# CAN.net
KiCad netlist of a schematic drawn in Altium Designer
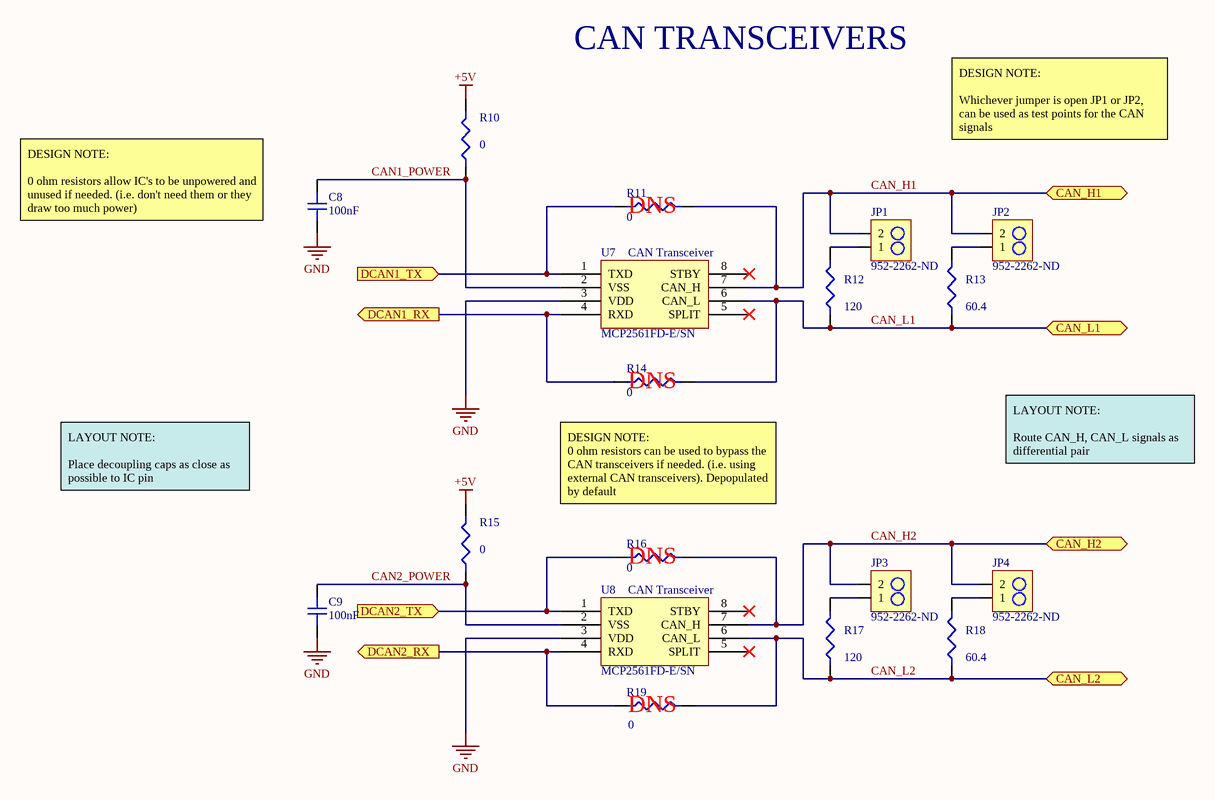
[diagram p0: CAN.SchDoc]

(export (version "E")
  (design (tool "Eeschema 10.0.6"))
  (components
    (comp (ref "C8")
      (value "100nF")
      (footprint "PHANTOM_FOOTPRINTS:C0805")
      (description "CAP MLCC 100nF 10Volts U2J 5%")
      (fields
        (field (name "MANUFACTURER") "Murata")
        (field (name "MANUFACTURER PART NUMBER") "GRM21B7U1A104JA01L")
      )
      (libsource (lib "PHANTOM_LIBRARY") (part "GRM21B7U1A104JA01L"))
    )
    (comp (ref "C9")
      (value "100nF")
      (footprint "PHANTOM_FOOTPRINTS:C0805")
      (description "CAP MLCC 100nF 10Volts U2J 5%")
      (fields
        (field (name "MANUFACTURER") "Murata")
        (field (name "MANUFACTURER PART NUMBER") "GRM21B7U1A104JA01L")
      )
      (libsource (lib "PHANTOM_LIBRARY") (part "GRM21B7U1A104JA01L"))
    )
    (comp (ref "JP1")
      (value "952-2262-ND")
      (footprint "2PIN_HEADER")
      (description "CONN_HeaderPins2pos Headers & Wire Housings 02 SIL VERTICAL PIN HEADER TIN")
      (fields (field (name "MANUFACTURER") "Harwin") (field (name "MANUFACTURER PART NUMBER") "M20-9990246"))
      (libsource (lib "PHANTOM_LIBRARY") (part "M20-9990246"))
    )
    (comp (ref "JP2")
      (value "952-2262-ND")
      (footprint "2PIN_HEADER")
      (description "CONN_HeaderPins2pos Headers & Wire Housings 02 SIL VERTICAL PIN HEADER TIN")
      (fields (field (name "MANUFACTURER") "Harwin") (field (name "MANUFACTURER PART NUMBER") "M20-9990246"))
      (libsource (lib "PHANTOM_LIBRARY") (part "M20-9990246"))
    )
    (comp (ref "JP3")
      (value "952-2262-ND")
      (footprint "2PIN_HEADER")
      (description "CONN_HeaderPins2pos Headers & Wire Housings 02 SIL VERTICAL PIN HEADER TIN")
      (fields (field (name "MANUFACTURER") "Harwin") (field (name "MANUFACTURER PART NUMBER") "M20-9990246"))
      (libsource (lib "PHANTOM_LIBRARY") (part "M20-9990246"))
    )
    (comp (ref "JP4")
      (value "952-2262-ND")
      (footprint "2PIN_HEADER")
      (description "CONN_HeaderPins2pos Headers & Wire Housings 02 SIL VERTICAL PIN HEADER TIN")
      (fields (field (name "MANUFACTURER") "Harwin") (field (name "MANUFACTURER PART NUMBER") "M20-9990246"))
      (libsource (lib "PHANTOM_LIBRARY") (part "M20-9990246"))
    )
    (comp (ref "R10")
      (value "0")
      (footprint "R0805")
      (description "RES SMD 0 OHM 1/8W 0805")
      (fields
        (field (name "MANUFACTURER") "Yageo")
        (field (name "MANUFACTURER PART NUMBER") "RC0805JR-070RL")
      )
      (libsource (lib "PHANTOM_LIBRARY") (part "RC0805JR-070RL"))
    )
    (comp (ref "R11")
      (value "0")
      (footprint "R0805")
      (description "RES SMD 0 OHM 1/8W 0805")
      (fields
        (field (name "MANUFACTURER") "Yageo")
        (field (name "MANUFACTURER PART NUMBER") "RC0805JR-070RL")
      )
      (libsource (lib "PHANTOM_LIBRARY") (part "RC0805JR-070RL"))
    )
    (comp (ref "R12")
      (value "120")
      (footprint "R0805")
      (description "RES SMD 120 OHM 1% 1/8W 0805")
      (fields
        (field (name "MANUFACTURER") "Yageo")
        (field (name "MANUFACTURER PART NUMBER") "RC0805FR-07120RL")
      )
      (libsource (lib "PHANTOM_LIBRARY") (part "RC0805FR-07120RL"))
    )
    (comp (ref "R13")
      (value "60.4")
      (footprint "R0805")
      (description "RES SMD 60.4 OHM 1% 1/8W 0805")
      (fields
        (field (name "MANUFACTURER") "Yageo")
        (field (name "MANUFACTURER PART NUMBER") "RC0805FR-0760R4L")
      )
      (libsource (lib "PHANTOM_LIBRARY") (part "RC0805FR-0760R4L"))
    )
    (comp (ref "R14")
      (value "0")
      (footprint "R0805")
      (description "RES SMD 0 OHM 1/8W 0805")
      (fields
        (field (name "MANUFACTURER") "Yageo")
        (field (name "MANUFACTURER PART NUMBER") "RC0805JR-070RL")
      )
      (libsource (lib "PHANTOM_LIBRARY") (part "RC0805JR-070RL"))
    )
    (comp (ref "R15")
      (value "0")
      (footprint "R0805")
      (description "RES SMD 0 OHM 1/8W 0805")
      (fields
        (field (name "MANUFACTURER") "Yageo")
        (field (name "MANUFACTURER PART NUMBER") "RC0805JR-070RL")
      )
      (libsource (lib "PHANTOM_LIBRARY") (part "RC0805JR-070RL"))
    )
    (comp (ref "R16")
      (value "0")
      (footprint "R0805")
      (description "RES SMD 0 OHM 1/8W 0805")
      (fields
        (field (name "MANUFACTURER") "Yageo")
        (field (name "MANUFACTURER PART NUMBER") "RC0805JR-070RL")
      )
      (libsource (lib "PHANTOM_LIBRARY") (part "RC0805JR-070RL"))
    )
    (comp (ref "R17")
      (value "120")
      (footprint "R0805")
      (description "RES SMD 120 OHM 1% 1/8W 0805")
      (fields
        (field (name "MANUFACTURER") "Yageo")
        (field (name "MANUFACTURER PART NUMBER") "RC0805FR-07120RL")
      )
      (libsource (lib "PHANTOM_LIBRARY") (part "RC0805FR-07120RL"))
    )
    (comp (ref "R18")
      (value "60.4")
      (footprint "R0805")
      (description "RES SMD 60.4 OHM 1% 1/8W 0805")
      (fields
        (field (name "MANUFACTURER") "Yageo")
        (field (name "MANUFACTURER PART NUMBER") "RC0805FR-0760R4L")
      )
      (libsource (lib "PHANTOM_LIBRARY") (part "RC0805FR-0760R4L"))
    )
    (comp (ref "R19")
      (value "0")
      (footprint "R0805")
      (description "RES SMD 0 OHM 1/8W 0805")
      (fields
        (field (name "MANUFACTURER") "Yageo")
        (field (name "MANUFACTURER PART NUMBER") "RC0805JR-070RL")
      )
      (libsource (lib "PHANTOM_LIBRARY") (part "RC0805JR-070RL"))
    )
    (comp (ref "U7")
      (value "MCP2561FD-E/SN")
      (footprint "8-SOIC_MCP2561")
      (description "IC CAN Bus, Transceiver, CAN, 1, 1, 4.5 V, 5.5 V, SOIC")
      (fields (field (name "MANUFACTURER") "Microchip"))
      (libsource (lib "PHANTOM_LIBRARY") (part "MCP2561FD-E/SN"))
    )
    (comp (ref "U8")
      (value "MCP2561FD-E/SN")
      (footprint "8-SOIC_MCP2561")
      (description "IC CAN Bus, Transceiver, CAN, 1, 1, 4.5 V, 5.5 V, SOIC")
      (fields (field (name "MANUFACTURER") "Microchip"))
      (libsource (lib "PHANTOM_LIBRARY") (part "MCP2561FD-E/SN"))
    )
  )
  (nets
    (net (code "1") (name "+5V") (class "Default")
      (node (ref "R10") (pin "2") (pinfunction "2_2") (pintype "passive"))
      (node (ref "R15") (pin "2") (pinfunction "2_2") (pintype "passive"))
    )
    (net (code "2") (name "/CAN1_POWER") (class "Default")
      (node (ref "C8") (pin "2") (pinfunction "2_2") (pintype "passive"))
      (node (ref "R10") (pin "1") (pinfunction "1_1") (pintype "passive"))
      (node (ref "U7") (pin "2") (pinfunction "VSS_2") (pintype "passive"))
    )
    (net (code "3") (name "/CAN2_POWER") (class "Default")
      (node (ref "C9") (pin "2") (pinfunction "2_2") (pintype "passive"))
      (node (ref "R15") (pin "1") (pinfunction "1_1") (pintype "passive"))
      (node (ref "U8") (pin "2") (pinfunction "VSS_2") (pintype "passive"))
    )
    (net (code "4") (name "/CAN_H1") (class "Default")
      (node (ref "JP1") (pin "2") (pinfunction "2_2") (pintype "passive"))
      (node (ref "JP2") (pin "2") (pinfunction "2_2") (pintype "passive"))
      (node (ref "R11") (pin "2") (pinfunction "2_2") (pintype "passive"))
      (node (ref "U7") (pin "7") (pinfunction "CAN_H_7") (pintype "passive"))
    )
    (net (code "5") (name "/CAN_H2") (class "Default")
      (node (ref "JP3") (pin "2") (pinfunction "2_2") (pintype "passive"))
      (node (ref "JP4") (pin "2") (pinfunction "2_2") (pintype "passive"))
      (node (ref "R16") (pin "2") (pinfunction "2_2") (pintype "passive"))
      (node (ref "U8") (pin "7") (pinfunction "CAN_H_7") (pintype "passive"))
    )
    (net (code "6") (name "/CAN_L1") (class "Default")
      (node (ref "R12") (pin "1") (pinfunction "1_1") (pintype "passive"))
      (node (ref "R13") (pin "1") (pinfunction "1_1") (pintype "passive"))
      (node (ref "R14") (pin "2") (pinfunction "2_2") (pintype "passive"))
      (node (ref "U7") (pin "6") (pinfunction "CAN_L_6") (pintype "passive"))
    )
    (net (code "7") (name "/CAN_L2") (class "Default")
      (node (ref "R17") (pin "1") (pinfunction "1_1") (pintype "passive"))
      (node (ref "R18") (pin "1") (pinfunction "1_1") (pintype "passive"))
      (node (ref "R19") (pin "2") (pinfunction "2_2") (pintype "passive"))
      (node (ref "U8") (pin "6") (pinfunction "CAN_L_6") (pintype "passive"))
    )
    (net (code "8") (name "/DCAN1_RX") (class "Default")
      (node (ref "R14") (pin "1") (pinfunction "1_1") (pintype "passive"))
      (node (ref "U7") (pin "4") (pinfunction "RXD_4") (pintype "passive"))
    )
    (net (code "9") (name "/DCAN1_TX") (class "Default")
      (node (ref "R11") (pin "1") (pinfunction "1_1") (pintype "passive"))
      (node (ref "U7") (pin "1") (pinfunction "TXD_1") (pintype "passive"))
    )
    (net (code "10") (name "/DCAN2_RX") (class "Default")
      (node (ref "R19") (pin "1") (pinfunction "1_1") (pintype "passive"))
      (node (ref "U8") (pin "4") (pinfunction "RXD_4") (pintype "passive"))
    )
    (net (code "11") (name "/DCAN2_TX") (class "Default")
      (node (ref "R16") (pin "1") (pinfunction "1_1") (pintype "passive"))
      (node (ref "U8") (pin "1") (pinfunction "TXD_1") (pintype "passive"))
    )
    (net (code "12") (name "GND") (class "Default")
      (node (ref "C8") (pin "1") (pinfunction "1_1") (pintype "passive"))
      (node (ref "C9") (pin "1") (pinfunction "1_1") (pintype "passive"))
      (node (ref "U7") (pin "3") (pinfunction "VDD_3") (pintype "passive"))
      (node (ref "U8") (pin "3") (pinfunction "VDD_3") (pintype "passive"))
    )
    (net (code "13") (name "Net-(JP1-Pad1)") (class "Default")
      (node (ref "JP1") (pin "1") (pinfunction "1_1") (pintype "passive"))
      (node (ref "R12") (pin "2") (pinfunction "2_2") (pintype "passive"))
    )
    (net (code "14") (name "Net-(JP2-Pad1)") (class "Default")
      (node (ref "JP2") (pin "1") (pinfunction "1_1") (pintype "passive"))
      (node (ref "R13") (pin "2") (pinfunction "2_2") (pintype "passive"))
    )
    (net (code "15") (name "Net-(JP3-Pad1)") (class "Default")
      (node (ref "JP3") (pin "1") (pinfunction "1_1") (pintype "passive"))
      (node (ref "R17") (pin "2") (pinfunction "2_2") (pintype "passive"))
    )
    (net (code "16") (name "Net-(JP4-Pad1)") (class "Default")
      (node (ref "JP4") (pin "1") (pinfunction "1_1") (pintype "passive"))
      (node (ref "R18") (pin "2") (pinfunction "2_2") (pintype "passive"))
    )
    (net (code "17") (name "unconnected-(U7-SPLIT-Pad5)") (class "Default")
      (node (ref "U7") (pin "5") (pinfunction "SPLIT_5") (pintype "passive+no_connect"))
    )
    (net (code "18") (name "unconnected-(U7-STBY-Pad8)") (class "Default")
      (node (ref "U7") (pin "8") (pinfunction "STBY_8") (pintype "passive+no_connect"))
    )
    (net (code "19") (name "unconnected-(U8-SPLIT-Pad5)") (class "Default")
      (node (ref "U8") (pin "5") (pinfunction "SPLIT_5") (pintype "passive+no_connect"))
    )
    (net (code "20") (name "unconnected-(U8-STBY-Pad8)") (class "Default")
      (node (ref "U8") (pin "8") (pinfunction "STBY_8") (pintype "passive+no_connect"))
    )
  )
)
